# lightstrip-driver.net
KiCad netlist of a schematic drawn in EAGLE
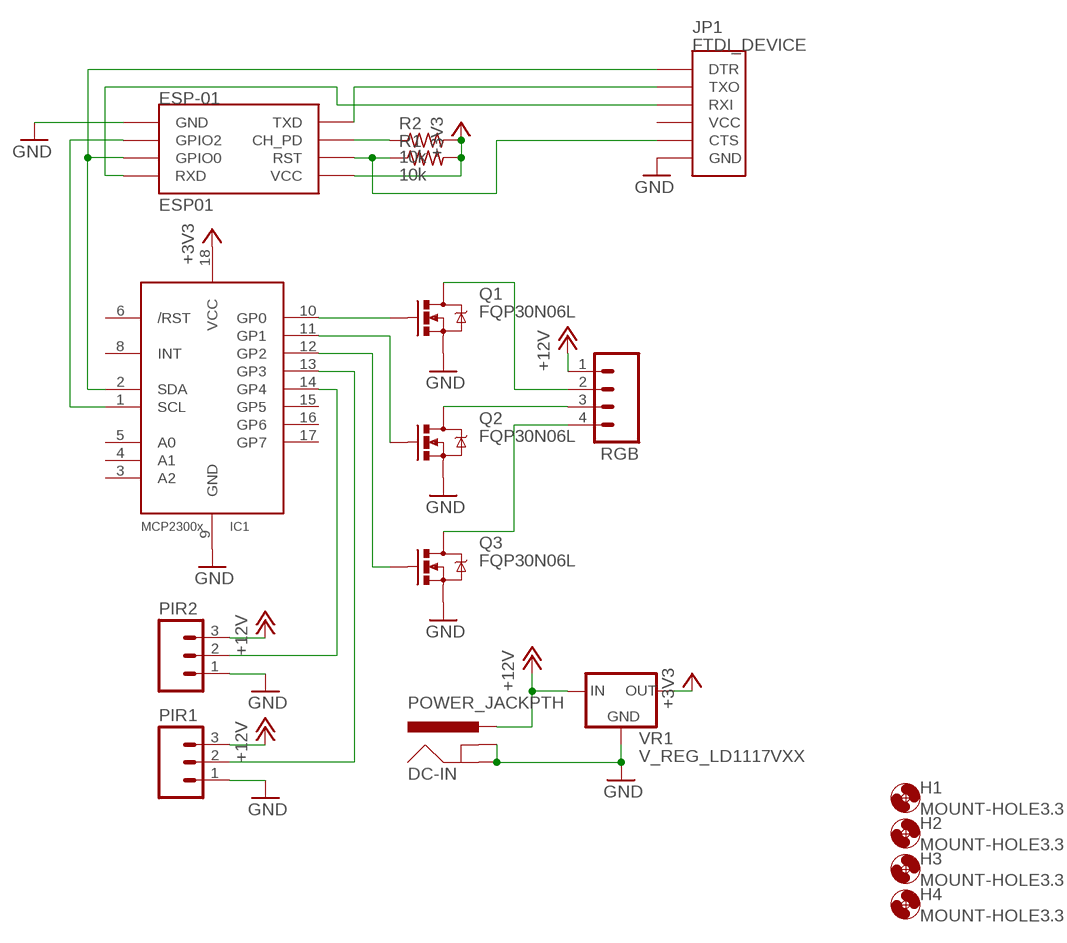
[diagram p0: schematic, sheet 1]

(export (version "E")
  (design (tool "Eeschema 10.0.6"))
  (components
    (comp (ref "DC-IN")
      (value "POWER_JACKPTH")
      (footprint "eagle-import:POWER_JACK_PTH")
      (libsource (lib "eagle-import") (part "POWER_JACKPTH"))
    )
    (comp (ref "ESP-01")
      (value "ESP01")
      (footprint "eagle-import:ESP01")
      (libsource (lib "eagle-import") (part "ESP01"))
    )
    (comp (ref "H1")
      (value "MOUNT-HOLE3.3")
      (footprint "eagle-import:3,3")
      (libsource (lib "eagle-import") (part "MOUNT-HOLE3.3"))
    )
    (comp (ref "H2")
      (value "MOUNT-HOLE3.3")
      (footprint "eagle-import:3,3")
      (libsource (lib "eagle-import") (part "MOUNT-HOLE3.3"))
    )
    (comp (ref "H3")
      (value "MOUNT-HOLE3.3")
      (footprint "eagle-import:3,3")
      (libsource (lib "eagle-import") (part "MOUNT-HOLE3.3"))
    )
    (comp (ref "H4")
      (value "MOUNT-HOLE3.3")
      (footprint "eagle-import:3,3")
      (libsource (lib "eagle-import") (part "MOUNT-HOLE3.3"))
    )
    (comp (ref "IC1")
      (value "MCP2300X/P")
      (footprint "eagle-import:DIL18")
      (libsource (lib "eagle-import") (part "MCP2300X/P"))
    )
    (comp (ref "JP1")
      (value "FTDI_DEVICE")
      (footprint "eagle-import:FTDI_DEVICE_SIDE")
      (libsource (lib "eagle-import") (part "FTDI_DEVICE"))
    )
    (comp (ref "PIR1")
      (value "M03PTH")
      (footprint "eagle-import:1X03")
      (libsource (lib "eagle-import") (part "M03PTH"))
    )
    (comp (ref "PIR2")
      (value "M03PTH")
      (footprint "eagle-import:1X03")
      (libsource (lib "eagle-import") (part "M03PTH"))
    )
    (comp (ref "Q1")
      (value "FQP30N06L")
      (footprint "eagle-import:TO220V")
      (libsource (lib "eagle-import") (part "MOSFET-NCHANNELFQP30N06L"))
    )
    (comp (ref "Q2")
      (value "FQP30N06L")
      (footprint "eagle-import:TO220V")
      (libsource (lib "eagle-import") (part "MOSFET-NCHANNELFQP30N06L"))
    )
    (comp (ref "Q3")
      (value "FQP30N06L")
      (footprint "eagle-import:TO220V")
      (libsource (lib "eagle-import") (part "MOSFET-NCHANNELFQP30N06L"))
    )
    (comp (ref "R1")
      (value "10k")
      (footprint "eagle-import:0207_7")
      (libsource (lib "eagle-import") (part "R-US_0207/7"))
    )
    (comp (ref "R2")
      (value "10k")
      (footprint "eagle-import:0207_7")
      (libsource (lib "eagle-import") (part "R-US_0207/7"))
    )
    (comp (ref "RGB")
      (value "M04PTH")
      (footprint "eagle-import:1X04")
      (libsource (lib "eagle-import") (part "M04PTH"))
    )
    (comp (ref "VR1")
      (value "V_REG_LD1117VXX")
      (footprint "eagle-import:78XXL")
      (libsource (lib "eagle-import") (part "V_REG_LD1117VXX"))
    )
  )
  (nets
    (net (code "1") (name "+3V3") (class "Default")
      (node (ref "ESP-01") (pin "VCC") (pinfunction "VCC_VCC") (pintype "bidirectional"))
      (node (ref "IC1") (pin "18") (pinfunction "VCC_18") (pintype "power_in"))
      (node (ref "R1") (pin "2") (pinfunction "2_2") (pintype "passive"))
      (node (ref "R2") (pin "2") (pinfunction "2_2") (pintype "passive"))
      (node (ref "VR1") (pin "GND") (pinfunction "OUT_GND") (pintype "passive"))
    )
    (net (code "2") (name "+12V") (class "Default")
      (node (ref "DC-IN") (pin "PWR") (pinfunction "PWR_PWR") (pintype "bidirectional"))
      (node (ref "PIR1") (pin "3") (pinfunction "3_3") (pintype "passive"))
      (node (ref "PIR2") (pin "3") (pinfunction "3_3") (pintype "passive"))
      (node (ref "RGB") (pin "1") (pinfunction "1_1") (pintype "passive"))
      (node (ref "VR1") (pin "OUT") (pinfunction "IN_OUT") (pintype "input"))
    )
    (net (code "3") (name "GND") (class "Default")
      (node (ref "DC-IN") (pin "GND") (pinfunction "GND_GND") (pintype "bidirectional"))
      (node (ref "DC-IN") (pin "GNDBREAK") (pinfunction "GNDBREAK_GNDBREAK") (pintype "bidirectional"))
      (node (ref "ESP-01") (pin "GND") (pinfunction "GND_GND") (pintype "bidirectional"))
      (node (ref "IC1") (pin "9") (pinfunction "GND_9") (pintype "power_in"))
      (node (ref "JP1") (pin "P$6") (pinfunction "GND_P$6") (pintype "bidirectional"))
      (node (ref "PIR1") (pin "1") (pinfunction "1_1") (pintype "passive"))
      (node (ref "PIR2") (pin "1") (pinfunction "1_1") (pintype "passive"))
      (node (ref "Q1") (pin "3") (pinfunction "S_3") (pintype "passive"))
      (node (ref "Q2") (pin "3") (pinfunction "S_3") (pintype "passive"))
      (node (ref "Q3") (pin "3") (pinfunction "S_3") (pintype "passive"))
      (node (ref "VR1") (pin "IN") (pinfunction "GND_IN") (pintype "input"))
    )
    (net (code "4") (name "Net-(ESP-01-PadCH_PD)") (class "Default")
      (node (ref "ESP-01") (pin "CH_PD") (pinfunction "CH_PD_CH_PD") (pintype "bidirectional"))
      (node (ref "R2") (pin "1") (pinfunction "1_1") (pintype "passive"))
    )
    (net (code "5") (name "Net-(ESP-01-RXD)") (class "Default")
      (node (ref "ESP-01") (pin "RX") (pinfunction "RXD_RX") (pintype "bidirectional"))
      (node (ref "JP1") (pin "P$3") (pinfunction "RXI_P$3") (pintype "bidirectional"))
    )
    (net (code "6") (name "Net-(ESP-01-TXD)") (class "Default")
      (node (ref "ESP-01") (pin "TX") (pinfunction "TXD_TX") (pintype "bidirectional"))
      (node (ref "JP1") (pin "P$2") (pinfunction "TXO_P$2") (pintype "bidirectional"))
    )
    (net (code "7") (name "Net-(IC1-GP0)") (class "Default")
      (node (ref "IC1") (pin "10") (pinfunction "GP0_10") (pintype "bidirectional"))
      (node (ref "Q1") (pin "1") (pinfunction "G_1") (pintype "passive"))
    )
    (net (code "8") (name "Net-(IC1-GP1)") (class "Default")
      (node (ref "IC1") (pin "11") (pinfunction "GP1_11") (pintype "bidirectional"))
      (node (ref "Q2") (pin "1") (pinfunction "G_1") (pintype "passive"))
    )
    (net (code "9") (name "Net-(IC1-GP2)") (class "Default")
      (node (ref "IC1") (pin "12") (pinfunction "GP2_12") (pintype "bidirectional"))
      (node (ref "Q3") (pin "1") (pinfunction "G_1") (pintype "passive"))
    )
    (net (code "10") (name "Net-(IC1-GP3)") (class "Default")
      (node (ref "IC1") (pin "13") (pinfunction "GP3_13") (pintype "bidirectional"))
      (node (ref "PIR1") (pin "2") (pinfunction "2_2") (pintype "passive"))
    )
    (net (code "11") (name "Net-(IC1-GP4)") (class "Default")
      (node (ref "IC1") (pin "14") (pinfunction "GP4_14") (pintype "bidirectional"))
      (node (ref "PIR2") (pin "2") (pinfunction "2_2") (pintype "passive"))
    )
    (net (code "12") (name "Net-(IC1-SCL)") (class "Default")
      (node (ref "ESP-01") (pin "GPIO2") (pinfunction "GPIO2_GPIO2") (pintype "bidirectional"))
      (node (ref "IC1") (pin "1") (pinfunction "SCL_1") (pintype "bidirectional"))
    )
    (net (code "13") (name "Net-(IC1-SDA)") (class "Default")
      (node (ref "ESP-01") (pin "GPIO0") (pinfunction "GPIO0_GPIO0") (pintype "bidirectional"))
      (node (ref "IC1") (pin "2") (pinfunction "SDA_2") (pintype "bidirectional"))
      (node (ref "JP1") (pin "P$1") (pinfunction "DTR_P$1") (pintype "bidirectional"))
    )
    (net (code "14") (name "Net-(JP1-CTS)") (class "Default")
      (node (ref "ESP-01") (pin "RST") (pinfunction "RST_RST") (pintype "bidirectional"))
      (node (ref "JP1") (pin "P$5") (pinfunction "CTS_P$5") (pintype "bidirectional"))
      (node (ref "R1") (pin "1") (pinfunction "1_1") (pintype "passive"))
    )
    (net (code "15") (name "Net-(Q1-D)") (class "Default")
      (node (ref "Q1") (pin "2") (pinfunction "D_2") (pintype "passive"))
      (node (ref "RGB") (pin "2") (pinfunction "2_2") (pintype "passive"))
    )
    (net (code "16") (name "Net-(Q2-D)") (class "Default")
      (node (ref "Q2") (pin "2") (pinfunction "D_2") (pintype "passive"))
      (node (ref "RGB") (pin "3") (pinfunction "3_3") (pintype "passive"))
    )
    (net (code "17") (name "Net-(Q3-D)") (class "Default")
      (node (ref "Q3") (pin "2") (pinfunction "D_2") (pintype "passive"))
      (node (ref "RGB") (pin "4") (pinfunction "4_4") (pintype "passive"))
    )
    (net (code "18") (name "unconnected-(IC1-A0-Pad5)") (class "Default")
      (node (ref "IC1") (pin "5") (pinfunction "A0_5") (pintype "input"))
    )
    (net (code "19") (name "unconnected-(IC1-A1-Pad4)") (class "Default")
      (node (ref "IC1") (pin "4") (pinfunction "A1_4") (pintype "input"))
    )
    (net (code "20") (name "unconnected-(IC1-A2-Pad3)") (class "Default")
      (node (ref "IC1") (pin "3") (pinfunction "A2_3") (pintype "input"))
    )
    (net (code "21") (name "unconnected-(IC1-GP5-Pad15)") (class "Default")
      (node (ref "IC1") (pin "15") (pinfunction "GP5_15") (pintype "bidirectional"))
    )
    (net (code "22") (name "unconnected-(IC1-GP6-Pad16)") (class "Default")
      (node (ref "IC1") (pin "16") (pinfunction "GP6_16") (pintype "bidirectional"))
    )
    (net (code "23") (name "unconnected-(IC1-GP7-Pad17)") (class "Default")
      (node (ref "IC1") (pin "17") (pinfunction "GP7_17") (pintype "bidirectional"))
    )
    (net (code "24") (name "unconnected-(IC1-INT-Pad8)") (class "Default")
      (node (ref "IC1") (pin "8") (pinfunction "INT_8") (pintype "output"))
    )
    (net (code "25") (name "unconnected-(IC1-{slash}RST-Pad6)") (class "Default")
      (node (ref "IC1") (pin "6") (pinfunction "/RST_6") (pintype "input"))
    )
    (net (code "26") (name "unconnected-(JP1-VCC-PadP$4)") (class "Default")
      (node (ref "JP1") (pin "P$4") (pinfunction "VCC_P$4") (pintype "bidirectional"))
    )
  )
)
